# CC254x_Board1.net
KiCad netlist of a schematic drawn in Altium Designer
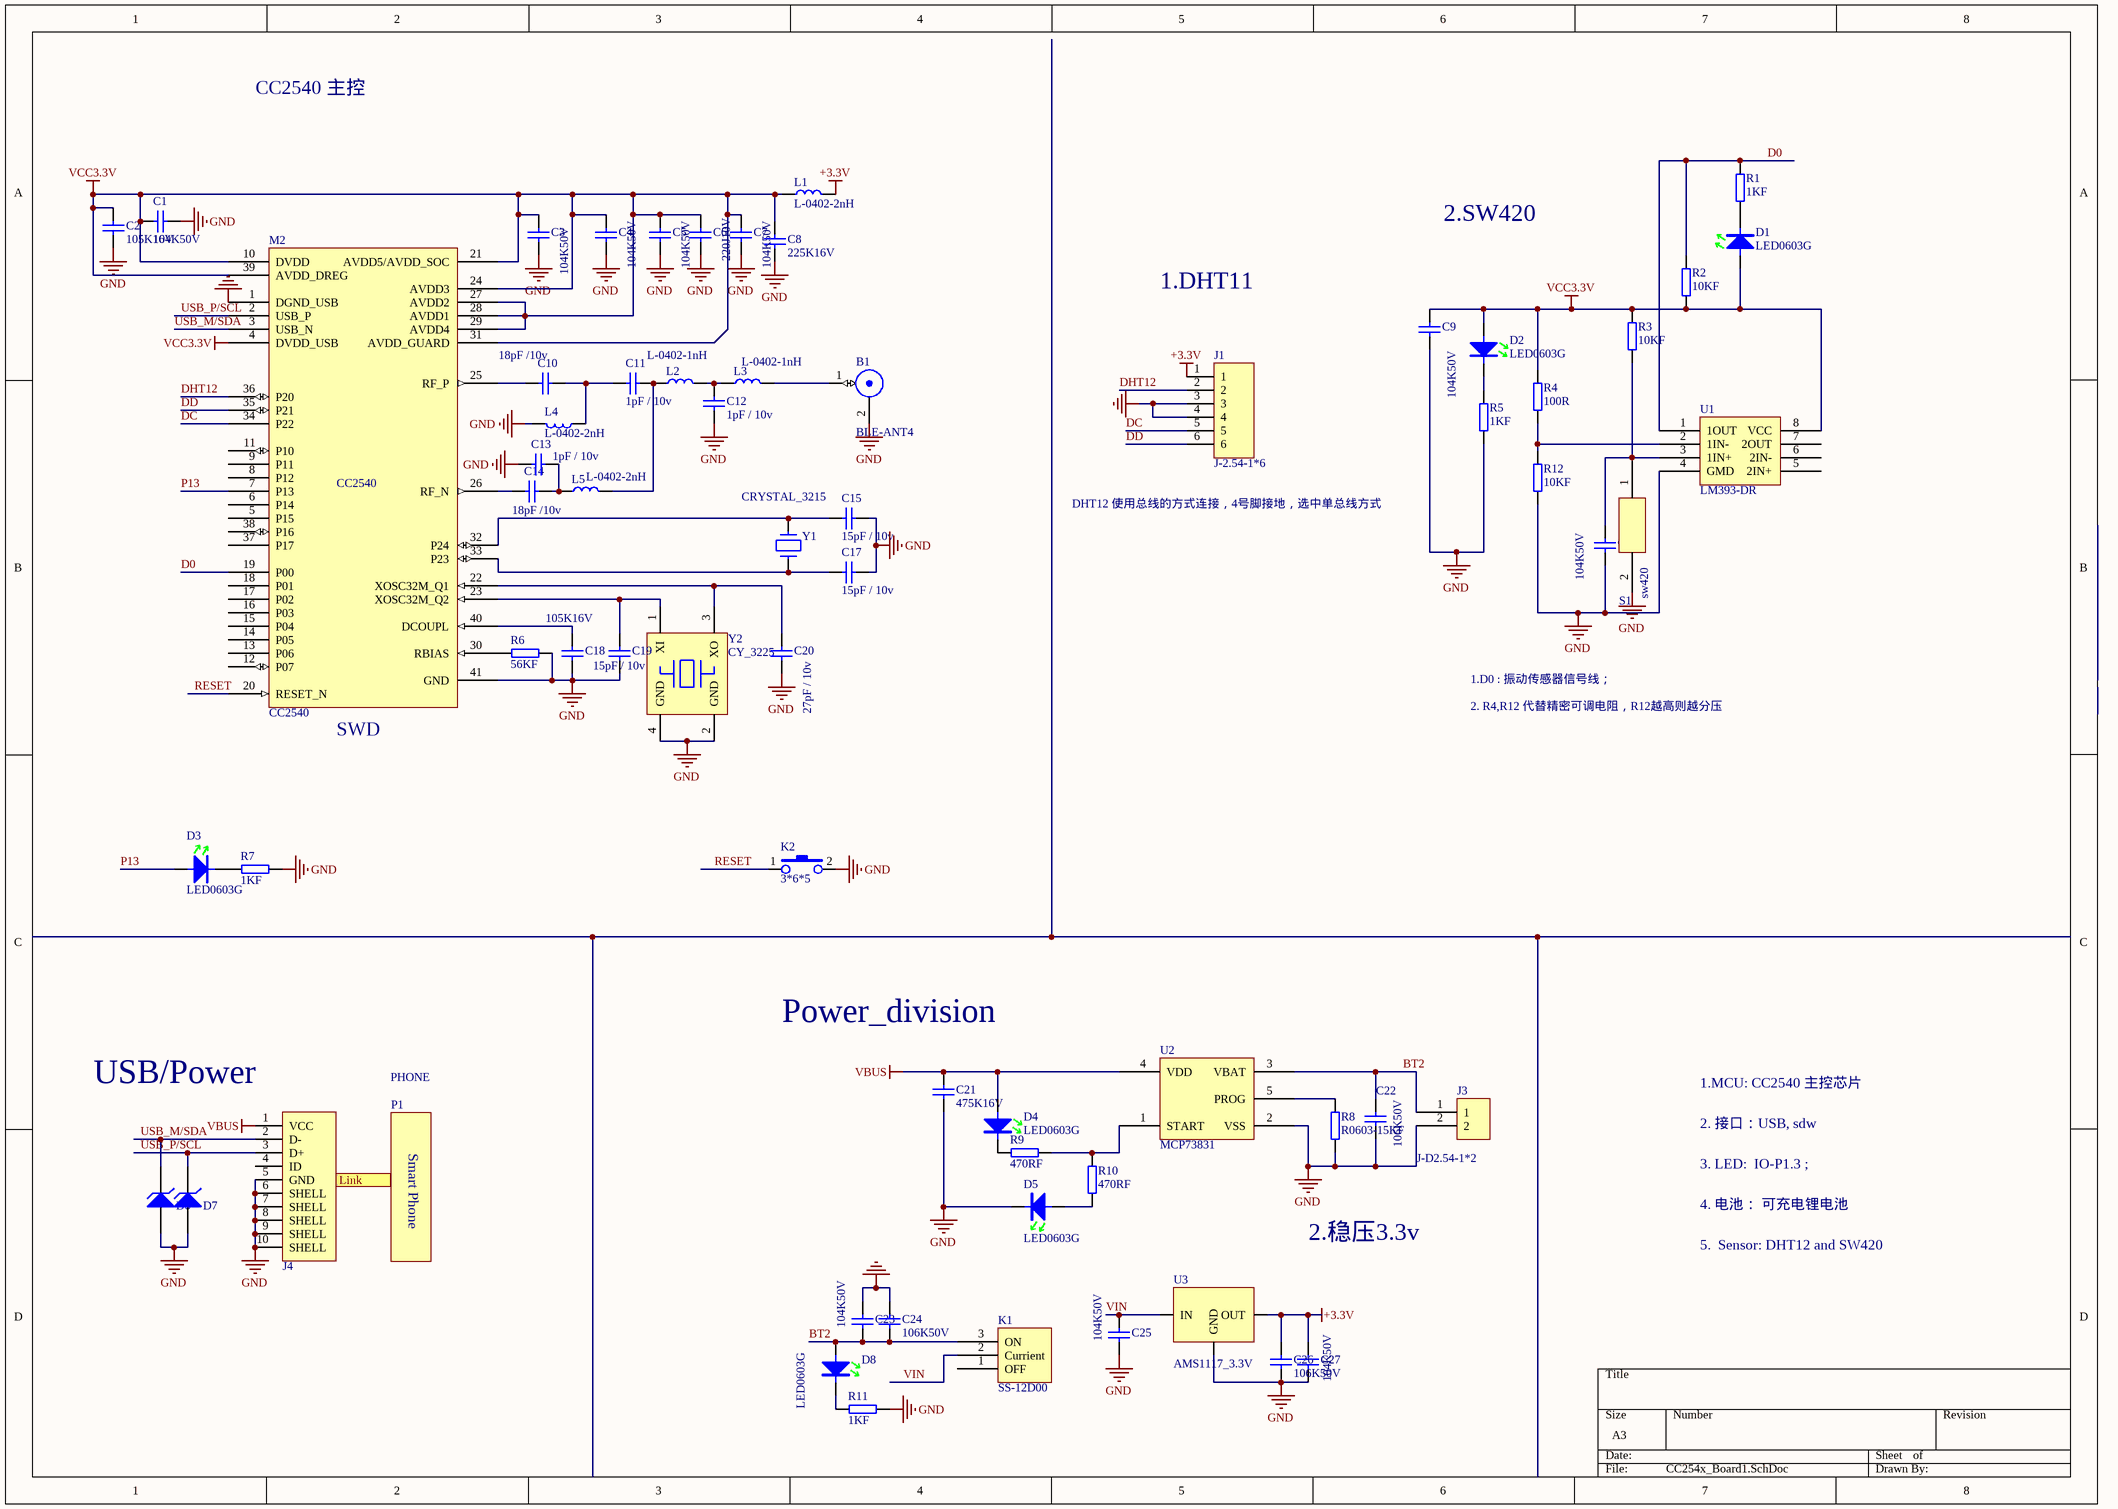
[diagram p0: CC254x_Board1.SchDoc]

(export (version "E")
  (design (tool "Eeschema 10.0.6"))
  (components
    (comp (ref "B1") (value "BLE-ANT4") (footprint "BLE-ANTS2") (libsource (lib "BleANT") (part "ANT")))
    (comp (ref "C1")
      (value "104K50V")
      (footprint "C0603")
      (description "贴片电容-陶瓷")
      (libsource (lib "Capacitor") (part "C0603X7R-104K50V"))
    )
    (comp (ref "C2")
      (value "105K16V")
      (footprint "C0603")
      (description "贴片电容-陶瓷")
      (libsource (lib "Capacitor") (part "C0603X7R-105K16V"))
    )
    (comp (ref "C3")
      (value "104K50V")
      (footprint "C0603")
      (description "贴片电容-陶瓷")
      (libsource (lib "Capacitor") (part "C0603X7R-104K50V"))
    )
    (comp (ref "C4")
      (value "104K50V")
      (footprint "C0603")
      (description "贴片电容-陶瓷")
      (libsource (lib "Capacitor") (part "C0603X7R-104K50V"))
    )
    (comp (ref "C5")
      (value "104K50V")
      (footprint "C0603")
      (description "贴片电容-陶瓷")
      (libsource (lib "Capacitor") (part "C0603X7R-104K50V"))
    )
    (comp (ref "C6")
      (value "220J10V")
      (footprint "C0402")
      (description "贴片电容-陶瓷")
      (libsource (lib "Capacitor") (part "C0402X7R-220J10V"))
    )
    (comp (ref "C7")
      (value "104K50V")
      (footprint "C0603")
      (description "贴片电容-陶瓷")
      (libsource (lib "Capacitor") (part "C0603X7R-104K50V"))
    )
    (comp (ref "C8")
      (value "225K16V")
      (footprint "C0603")
      (description "贴片电容-陶瓷")
      (libsource (lib "Capacitor") (part "C0603X7R-225K16V"))
    )
    (comp (ref "C9")
      (value "104K50V")
      (footprint "C0603")
      (description "贴片电容-陶瓷")
      (libsource (lib "Capacitor") (part "C0603X7R-104K50V"))
    )
    (comp (ref "C10")
      (value "18pF /10v")
      (footprint "C0402")
      (description "贴片电容-陶瓷")
      (libsource (lib "Capacitor") (part "C0402X7R-101J10V"))
    )
    (comp (ref "C11")
      (value "1pF / 10v")
      (footprint "C0402")
      (description "贴片电容-陶瓷")
      (libsource (lib "Capacitor") (part "C0402X7R-101J10V"))
    )
    (comp (ref "C12")
      (value "1pF / 10v")
      (footprint "C0402")
      (description "贴片电容-陶瓷")
      (libsource (lib "Capacitor") (part "C0402X7R-101J10V"))
    )
    (comp (ref "C13")
      (value "1pF / 10v")
      (footprint "C0402")
      (description "贴片电容-陶瓷")
      (libsource (lib "Capacitor") (part "C0402X7R-101J10V"))
    )
    (comp (ref "C14")
      (value "18pF /10v")
      (footprint "C0402")
      (description "贴片电容-陶瓷")
      (libsource (lib "Capacitor") (part "C0402X7R-101J10V"))
    )
    (comp (ref "C15")
      (value "15pF / 10v")
      (footprint "C0402")
      (description "贴片电容-陶瓷")
      (libsource (lib "Capacitor") (part "C0402X7R-101J10V"))
    )
    (comp (ref "C16")
      (value "104K50V")
      (footprint "C0603")
      (description "贴片电容-陶瓷")
      (libsource (lib "Capacitor") (part "C0603X7R-104K50V"))
    )
    (comp (ref "C17")
      (value "15pF / 10v")
      (footprint "C0402")
      (description "贴片电容-陶瓷")
      (libsource (lib "Capacitor") (part "C0402X7R-101J10V"))
    )
    (comp (ref "C18")
      (value "105K16V")
      (footprint "C0603")
      (description "贴片电容-陶瓷")
      (libsource (lib "Capacitor") (part "C0603X7R-105K16V"))
    )
    (comp (ref "C19")
      (value "15pF / 10v")
      (footprint "C0402")
      (description "贴片电容-陶瓷")
      (libsource (lib "Capacitor") (part "C0402X7R-101J10V"))
    )
    (comp (ref "C20")
      (value "27pF / 10v")
      (footprint "C0402")
      (description "贴片电容-陶瓷")
      (libsource (lib "Capacitor") (part "C0402X7R-101J10V"))
    )
    (comp (ref "C21")
      (value "475K16V")
      (footprint "C0603")
      (description "贴片电容-陶瓷")
      (libsource (lib "Capacitor") (part "C0603X7R-475K16V"))
    )
    (comp (ref "C22")
      (value "106K50V")
      (footprint "C0603")
      (description "贴片电容-陶瓷")
      (libsource (lib "Capacitor") (part "C0603X7R-106K50V"))
    )
    (comp (ref "C23")
      (value "104K50V")
      (footprint "C0603")
      (description "贴片电容-陶瓷")
      (libsource (lib "Capacitor") (part "C0603X7R-104K50V"))
    )
    (comp (ref "C24")
      (value "106K50V")
      (footprint "C0603")
      (description "贴片电容-陶瓷")
      (libsource (lib "Capacitor") (part "C0603X7R-106K50V"))
    )
    (comp (ref "C25")
      (value "104K50V")
      (footprint "C0603")
      (description "贴片电容-陶瓷")
      (libsource (lib "Capacitor") (part "C0603X7R-104K50V"))
    )
    (comp (ref "C26")
      (value "106K50V")
      (footprint "C0603")
      (description "贴片电容-陶瓷")
      (libsource (lib "Capacitor") (part "C0603X7R-106K50V"))
    )
    (comp (ref "C27")
      (value "104K50V")
      (footprint "C0603")
      (description "贴片电容-陶瓷")
      (libsource (lib "Capacitor") (part "C0603X7R-104K50V"))
    )
    (comp (ref "D1")
      (value "LED0603G")
      (footprint "D-LED0603G")
      (description "贴片二极管-LED")
      (libsource (lib "Diode") (part "DLED-0603-G"))
    )
    (comp (ref "D2")
      (value "LED0603G")
      (footprint "D-LED0603G")
      (description "贴片二极管-LED")
      (libsource (lib "Diode") (part "DLED-0603-G"))
    )
    (comp (ref "D3")
      (value "LED0603G")
      (footprint "D-LED0603G")
      (description "贴片二极管-LED")
      (libsource (lib "aiwacV2.0") (part "DLED-0603-G"))
    )
    (comp (ref "D4")
      (value "LED0603G")
      (footprint "D-LED0603G")
      (description "贴片二极管-LED")
      (libsource (lib "Diode") (part "DLED-0603-G"))
    )
    (comp (ref "D5")
      (value "LED0603G")
      (footprint "D-LED0603G")
      (description "贴片二极管-LED")
      (libsource (lib "Diode") (part "DLED-0603-G"))
    )
    (comp (ref "D6")
      (value "ESDA_TR1/0603")
      (footprint "HS_0603D")
      (description "Zener Diode")
      (fields (field (name "PUBLISHER") "*"))
      (libsource (lib "aiwacV2.0") (part "D Zener"))
    )
    (comp (ref "D7")
      (value "ESDA_TR1/0603")
      (footprint "HS_0603D")
      (description "Zener Diode")
      (fields (field (name "PUBLISHER") "*"))
      (libsource (lib "aiwacV2.0") (part "D Zener"))
    )
    (comp (ref "D8")
      (value "LED0603G")
      (footprint "D-LED0603G")
      (description "贴片二极管-LED")
      (libsource (lib "aiwacV2.0") (part "DLED-0603-G"))
    )
    (comp (ref "J1")
      (value "J-2.54-1*6")
      (footprint "D2.54-1*6")
      (description "单排")
      (libsource (lib "Connector") (part "J-2.54-6"))
    )
    (comp (ref "J3")
      (value "J-D2.54-1*2")
      (footprint "D2.54-1*2P")
      (libsource (lib "Connector") (part "J-D2.54-1*2单排"))
    )
    (comp (ref "J4")
      (value "USB-MINI-SOCKET")
      (footprint "MICRO-USB - 5.9")
      (description "USB-A卧式插座")
      (libsource (lib "epic2") (part "J-USB-MINI-SOCKET"))
    )
    (comp (ref "K1")
      (value "SS-12D00")
      (footprint "SS-12D00")
      (libsource (lib "Key") (part "SS-12D00(1P2T) 立式 柄高5MM"))
    )
    (comp (ref "K2")
      (value "3*6*5")
      (footprint "S-K3*6")
      (description "贴片-卧式轻触开关")
      (libsource (lib "Key") (part "3*6*5"))
    )
    (comp (ref "L1")
      (value "L-0402-2nH")
      (footprint "L0402")
      (description "贴片电感-层叠")
      (libsource (lib "magnetic") (part "L-0402-2nH"))
    )
    (comp (ref "L2")
      (value "L-0402-1nH")
      (footprint "L0402")
      (description "贴片电感-层叠")
      (libsource (lib "magnetic") (part "L-0402-2.2nH"))
    )
    (comp (ref "L3")
      (value "L-0402-1nH")
      (footprint "L0402")
      (description "贴片电感-层叠")
      (libsource (lib "magnetic") (part "L-0402-2.2nH"))
    )
    (comp (ref "L4")
      (value "L-0402-2nH")
      (footprint "L0402")
      (description "贴片电感-层叠")
      (libsource (lib "magnetic") (part "L-0402-2nH"))
    )
    (comp (ref "L5")
      (value "L-0402-2nH")
      (footprint "L0402")
      (description "贴片电感-层叠")
      (libsource (lib "magnetic") (part "L-0402-2nH"))
    )
    (comp (ref "M2")
      (value "CC2540")
      (footprint "CC254X_QFN")
      (libsource (lib "CC254xEM-sch") (part "CC2540"))
    )
    (comp (ref "P1") (value "PHONE") (libsource (lib "epic") (part "PHONE")))
    (comp (ref "R1")
      (value "1KF")
      (footprint "R0603")
      (description "贴片电阻-通用")
      (libsource (lib "Resistor") (part "R0603-1KF"))
    )
    (comp (ref "R2")
      (value "10KF")
      (footprint "R0603")
      (description "贴片电阻-通用")
      (libsource (lib "Resistor") (part "R0603-10KF"))
    )
    (comp (ref "R3")
      (value "10KF")
      (footprint "R0603")
      (description "贴片电阻-通用")
      (libsource (lib "Resistor") (part "R0603-10KF"))
    )
    (comp (ref "R4")
      (value "100R")
      (footprint "R0603")
      (description "贴片电阻-通用")
      (libsource (lib "Resistor") (part "R0603-10KF"))
    )
    (comp (ref "R5")
      (value "1KF")
      (footprint "R0603")
      (description "贴片电阻-通用")
      (libsource (lib "Resistor") (part "R0603-1KF"))
    )
    (comp (ref "R6")
      (value "56KF")
      (footprint "R0603")
      (description "贴片电阻-通用")
      (libsource (lib "Resistor") (part "R0603-47KF"))
    )
    (comp (ref "R7")
      (value "1KF")
      (footprint "R0603")
      (description "贴片电阻-通用")
      (libsource (lib "Resistor") (part "R0603-1KF"))
    )
    (comp (ref "R8")
      (value "R0603-15KF")
      (footprint "R0603")
      (description "贴片电容-通用")
      (libsource (lib "Resistor") (part "R0603-15KF"))
    )
    (comp (ref "R9")
      (value "470RF")
      (footprint "R0603")
      (description "贴片电阻-通用")
      (libsource (lib "Resistor") (part "R0603-470RF"))
    )
    (comp (ref "R10")
      (value "470RF")
      (footprint "R0603")
      (description "贴片电阻-通用")
      (libsource (lib "Resistor") (part "R0603-470RF"))
    )
    (comp (ref "R11")
      (value "1KF")
      (footprint "R0603")
      (description "贴片电阻-通用")
      (libsource (lib "Resistor") (part "R0603-1KF"))
    )
    (comp (ref "R12")
      (value "10KF")
      (footprint "R0603")
      (description "贴片电阻-通用")
      (libsource (lib "Resistor") (part "R0603-10KF"))
    )
    (comp (ref "S1")
      (value "sw420")
      (footprint "sw420")
      (description "常闭振动传感器")
      (libsource (lib "sensor") (part "sw420"))
    )
    (comp (ref "U1")
      (value "LM393-DR")
      (footprint "LM393")
      (description "双路比较器")
      (libsource (lib "IC") (part "LM393-DR"))
    )
    (comp (ref "U2")
      (value "MCP73831")
      (footprint "SOT23-5N")
      (description "charge IC")
      (libsource (lib "IC") (part "MCP73831"))
    )
    (comp (ref "U3")
      (value "AMS1117_3.3V")
      (footprint "SOT-223")
      (libsource (lib "IC") (part "AMS1117-3.3V"))
    )
    (comp (ref "Y1")
      (value "CRYSTAL_3215")
      (footprint "CRYSTAL_3215")
      (description "CRYSTAL_3215，两脚")
      (libsource (lib "oscillator") (part "CRYSTAL_3215"))
    )
    (comp (ref "Y2") (value "CY_3225") (footprint "CY_3225") (libsource (lib "oscillator") (part "CY_3225")))
  )
  (nets
    (net (code "1") (name "+3.3V") (class "Default")
      (node (ref "C26") (pin "2") (pinfunction "2_2") (pintype "passive"))
      (node (ref "C27") (pin "1") (pinfunction "1_1") (pintype "passive"))
      (node (ref "J1") (pin "1") (pinfunction "1_1") (pintype "passive"))
      (node (ref "L1") (pin "2") (pinfunction "2_2") (pintype "passive"))
      (node (ref "U3") (pin "2") (pinfunction "OUT_2") (pintype "passive"))
    )
    (net (code "2") (name "/BT2") (class "Default")
      (node (ref "C22") (pin "1") (pinfunction "1_1") (pintype "passive"))
      (node (ref "C23") (pin "2") (pinfunction "2_2") (pintype "passive"))
      (node (ref "C24") (pin "1") (pinfunction "1_1") (pintype "passive"))
      (node (ref "D8") (pin "1") (pinfunction "1_1") (pintype "passive"))
      (node (ref "J3") (pin "1") (pinfunction "1_1") (pintype "passive"))
      (node (ref "K1") (pin "3") (pinfunction "ON_3") (pintype "passive"))
      (node (ref "U2") (pin "3") (pinfunction "VBAT_3") (pintype "passive"))
    )
    (net (code "3") (name "/D0") (class "Default")
      (node (ref "M2") (pin "19") (pinfunction "P00_19") (pintype "passive"))
      (node (ref "R1") (pin "1") (pinfunction "1_1") (pintype "passive"))
      (node (ref "R2") (pin "2") (pinfunction "2_2") (pintype "passive"))
      (node (ref "U1") (pin "1") (pinfunction "1OUT_1") (pintype "passive"))
    )
    (net (code "4") (name "/DC") (class "Default")
      (node (ref "J1") (pin "5") (pinfunction "5_5") (pintype "passive"))
      (node (ref "M2") (pin "34") (pinfunction "P22_34") (pintype "passive"))
    )
    (net (code "5") (name "/DD") (class "Default")
      (node (ref "J1") (pin "6") (pinfunction "6_6") (pintype "passive"))
      (node (ref "M2") (pin "35") (pinfunction "P21_35") (pintype "bidirectional"))
    )
    (net (code "6") (name "/DHT12") (class "Default")
      (node (ref "J1") (pin "2") (pinfunction "2_2") (pintype "passive"))
      (node (ref "M2") (pin "36") (pinfunction "P20_36") (pintype "bidirectional"))
    )
    (net (code "8") (name "/P13") (class "Default")
      (node (ref "D3") (pin "1") (pinfunction "1_1") (pintype "passive"))
      (node (ref "M2") (pin "7") (pinfunction "P13_7") (pintype "passive"))
    )
    (net (code "9") (name "/RESET") (class "Default")
      (node (ref "K2") (pin "1") (pinfunction "1_1") (pintype "passive"))
      (node (ref "M2") (pin "20") (pinfunction "RESET_N_20") (pintype "input"))
    )
    (net (code "10") (name "/USB_M{slash}SDA") (class "Default")
      (node (ref "D6") (pin "2") (pinfunction "K_2") (pintype "passive"))
      (node (ref "J4") (pin "2") (pinfunction "D-_2") (pintype "passive"))
      (node (ref "M2") (pin "3") (pinfunction "USB_N_3") (pintype "power_in"))
    )
    (net (code "11") (name "/USB_P{slash}SCL") (class "Default")
      (node (ref "D7") (pin "2") (pinfunction "K_2") (pintype "passive"))
      (node (ref "J4") (pin "3") (pinfunction "D+_3") (pintype "passive"))
      (node (ref "M2") (pin "2") (pinfunction "USB_P_2") (pintype "power_in"))
    )
    (net (code "12") (name "/VIN") (class "Default")
      (node (ref "C25") (pin "1") (pinfunction "1_1") (pintype "passive"))
      (node (ref "K1") (pin "2") (pinfunction "Currient_2") (pintype "passive"))
      (node (ref "U3") (pin "3") (pinfunction "IN_3") (pintype "passive"))
    )
    (net (code "13") (name "GND") (class "Default")
      (node (ref "B1") (pin "2") (pinfunction "2_2") (pintype "power_in"))
      (node (ref "C1") (pin "2") (pinfunction "2_2") (pintype "passive"))
      (node (ref "C12") (pin "2") (pinfunction "2_2") (pintype "passive"))
      (node (ref "C13") (pin "2") (pinfunction "2_2") (pintype "passive"))
      (node (ref "C15") (pin "2") (pinfunction "2_2") (pintype "passive"))
      (node (ref "C16") (pin "2") (pinfunction "2_2") (pintype "passive"))
      (node (ref "C17") (pin "2") (pinfunction "2_2") (pintype "passive"))
      (node (ref "C18") (pin "1") (pinfunction "1_1") (pintype "passive"))
      (node (ref "C19") (pin "2") (pinfunction "2_2") (pintype "passive"))
      (node (ref "C2") (pin "1") (pinfunction "1_1") (pintype "passive"))
      (node (ref "C20") (pin "2") (pinfunction "2_2") (pintype "passive"))
      (node (ref "C21") (pin "2") (pinfunction "2_2") (pintype "passive"))
      (node (ref "C22") (pin "2") (pinfunction "2_2") (pintype "passive"))
      (node (ref "C23") (pin "1") (pinfunction "1_1") (pintype "passive"))
      (node (ref "C24") (pin "2") (pinfunction "2_2") (pintype "passive"))
      (node (ref "C25") (pin "2") (pinfunction "2_2") (pintype "passive"))
      (node (ref "C26") (pin "1") (pinfunction "1_1") (pintype "passive"))
      (node (ref "C27") (pin "2") (pinfunction "2_2") (pintype "passive"))
      (node (ref "C3") (pin "1") (pinfunction "1_1") (pintype "passive"))
      (node (ref "C4") (pin "1") (pinfunction "1_1") (pintype "passive"))
      (node (ref "C5") (pin "1") (pinfunction "1_1") (pintype "passive"))
      (node (ref "C6") (pin "2") (pinfunction "2_2") (pintype "passive"))
      (node (ref "C7") (pin "1") (pinfunction "1_1") (pintype "passive"))
      (node (ref "C8") (pin "2") (pinfunction "2_2") (pintype "passive"))
      (node (ref "C9") (pin "2") (pinfunction "2_2") (pintype "passive"))
      (node (ref "D5") (pin "2") (pinfunction "2_2") (pintype "passive"))
      (node (ref "D6") (pin "1") (pinfunction "A_1") (pintype "passive"))
      (node (ref "D7") (pin "1") (pinfunction "A_1") (pintype "passive"))
      (node (ref "J1") (pin "3") (pinfunction "3_3") (pintype "passive"))
      (node (ref "J1") (pin "4") (pinfunction "4_4") (pintype "passive"))
      (node (ref "J3") (pin "2") (pinfunction "2_2") (pintype "passive"))
      (node (ref "J4") (pin "10") (pinfunction "SHELL_10") (pintype "passive"))
      (node (ref "J4") (pin "5") (pinfunction "GND_5") (pintype "passive"))
      (node (ref "J4") (pin "6") (pinfunction "SHELL_6") (pintype "passive"))
      (node (ref "J4") (pin "7") (pinfunction "SHELL_7") (pintype "passive"))
      (node (ref "J4") (pin "8") (pinfunction "SHELL_8") (pintype "passive"))
      (node (ref "J4") (pin "9") (pinfunction "SHELL_9") (pintype "passive"))
      (node (ref "K2") (pin "2") (pinfunction "2_2") (pintype "passive"))
      (node (ref "L4") (pin "2") (pinfunction "2_2") (pintype "passive"))
      (node (ref "M2") (pin "1") (pinfunction "DGND_USB_1") (pintype "power_in"))
      (node (ref "M2") (pin "41") (pinfunction "GND_41") (pintype "power_in"))
      (node (ref "R11") (pin "2") (pinfunction "2_2") (pintype "passive"))
      (node (ref "R12") (pin "1") (pinfunction "1_1") (pintype "passive"))
      (node (ref "R5") (pin "1") (pinfunction "1_1") (pintype "passive"))
      (node (ref "R6") (pin "2") (pinfunction "2_2") (pintype "passive"))
      (node (ref "R7") (pin "2") (pinfunction "2_2") (pintype "passive"))
      (node (ref "R8") (pin "1") (pinfunction "1_1") (pintype "passive"))
      (node (ref "U1") (pin "4") (pinfunction "GMD_4") (pintype "passive"))
      (node (ref "U2") (pin "2") (pinfunction "VSS_2") (pintype "passive"))
      (node (ref "U3") (pin "1") (pinfunction "GND_1") (pintype "passive"))
      (node (ref "Y2") (pin "2") (pinfunction "GND_2") (pintype "passive"))
      (node (ref "Y2") (pin "4") (pinfunction "GND_4") (pintype "passive"))
    )
    (net (code "14") (name "Net-(B1-Pad1)") (class "Default")
      (node (ref "B1") (pin "1") (pinfunction "1_1") (pintype "bidirectional"))
      (node (ref "L3") (pin "2") (pinfunction "2_2") (pintype "passive"))
    )
    (net (code "15") (name "Net-(C10-Pad1)") (class "Default")
      (node (ref "C10") (pin "1") (pinfunction "1_1") (pintype "passive"))
      (node (ref "C11") (pin "2") (pinfunction "2_2") (pintype "passive"))
      (node (ref "L4") (pin "1") (pinfunction "1_1") (pintype "passive"))
    )
    (net (code "16") (name "Net-(C11-Pad1)") (class "Default")
      (node (ref "C11") (pin "1") (pinfunction "1_1") (pintype "passive"))
      (node (ref "L2") (pin "1") (pinfunction "1_1") (pintype "passive"))
      (node (ref "L5") (pin "2") (pinfunction "2_2") (pintype "passive"))
    )
    (net (code "17") (name "Net-(C12-Pad1)") (class "Default")
      (node (ref "C12") (pin "1") (pinfunction "1_1") (pintype "passive"))
      (node (ref "L2") (pin "2") (pinfunction "2_2") (pintype "passive"))
      (node (ref "L3") (pin "1") (pinfunction "1_1") (pintype "passive"))
    )
    (net (code "18") (name "Net-(C13-Pad1)") (class "Default")
      (node (ref "C13") (pin "1") (pinfunction "1_1") (pintype "passive"))
      (node (ref "C14") (pin "1") (pinfunction "1_1") (pintype "passive"))
      (node (ref "L5") (pin "1") (pinfunction "1_1") (pintype "passive"))
    )
    (net (code "19") (name "Net-(D1-Pad2)") (class "Default")
      (node (ref "D1") (pin "2") (pinfunction "2_2") (pintype "passive"))
      (node (ref "R1") (pin "2") (pinfunction "2_2") (pintype "passive"))
    )
    (net (code "20") (name "Net-(D2-Pad2)") (class "Default")
      (node (ref "D2") (pin "2") (pinfunction "2_2") (pintype "passive"))
      (node (ref "R5") (pin "2") (pinfunction "2_2") (pintype "passive"))
    )
    (net (code "21") (name "Net-(D3-Pad2)") (class "Default")
      (node (ref "D3") (pin "2") (pinfunction "2_2") (pintype "passive"))
      (node (ref "R7") (pin "1") (pinfunction "1_1") (pintype "passive"))
    )
    (net (code "22") (name "Net-(D4-Pad2)") (class "Default")
      (node (ref "D4") (pin "2") (pinfunction "2_2") (pintype "passive"))
      (node (ref "R9") (pin "1") (pinfunction "1_1") (pintype "passive"))
    )
    (net (code "23") (name "Net-(D5-Pad1)") (class "Default")
      (node (ref "D5") (pin "1") (pinfunction "1_1") (pintype "passive"))
      (node (ref "R10") (pin "1") (pinfunction "1_1") (pintype "passive"))
    )
    (net (code "24") (name "Net-(D8-Pad2)") (class "Default")
      (node (ref "D8") (pin "2") (pinfunction "2_2") (pintype "passive"))
      (node (ref "R11") (pin "1") (pinfunction "1_1") (pintype "passive"))
    )
    (net (code "25") (name "Net-(M2-DCOUPL)") (class "Default")
      (node (ref "C18") (pin "2") (pinfunction "2_2") (pintype "passive"))
      (node (ref "M2") (pin "40") (pinfunction "DCOUPL_40") (pintype "input"))
    )
    (net (code "26") (name "Net-(M2-P23)") (class "Default")
      (node (ref "C17") (pin "1") (pinfunction "1_1") (pintype "passive"))
      (node (ref "M2") (pin "33") (pinfunction "P23_33") (pintype "bidirectional"))
      (node (ref "Y1") (pin "1") (pinfunction "1_1") (pintype "passive"))
    )
    (net (code "27") (name "Net-(M2-P24)") (class "Default")
      (node (ref "C15") (pin "1") (pinfunction "1_1") (pintype "passive"))
      (node (ref "M2") (pin "32") (pinfunction "P24_32") (pintype "bidirectional"))
      (node (ref "Y1") (pin "2") (pinfunction "2_2") (pintype "passive"))
    )
    (net (code "28") (name "Net-(M2-RBIAS)") (class "Default")
      (node (ref "M2") (pin "30") (pinfunction "RBIAS_30") (pintype "input"))
      (node (ref "R6") (pin "1") (pinfunction "1_1") (pintype "passive"))
    )
    (net (code "29") (name "Net-(M2-RF_N)") (class "Default")
      (node (ref "C14") (pin "2") (pinfunction "2_2") (pintype "passive"))
      (node (ref "M2") (pin "26") (pinfunction "RF_N_26") (pintype "output"))
    )
    (net (code "30") (name "Net-(M2-RF_P)") (class "Default")
      (node (ref "C10") (pin "2") (pinfunction "2_2") (pintype "passive"))
      (node (ref "M2") (pin "25") (pinfunction "RF_P_25") (pintype "output"))
    )
    (net (code "31") (name "Net-(M2-XOSC32M_Q1)") (class "Default")
      (node (ref "C20") (pin "1") (pinfunction "1_1") (pintype "passive"))
      (node (ref "M2") (pin "22") (pinfunction "XOSC32M_Q1_22") (pintype "input"))
      (node (ref "Y2") (pin "3") (pinfunction "XO_3") (pintype "passive"))
    )
    (net (code "32") (name "Net-(M2-XOSC32M_Q2)") (class "Default")
      (node (ref "C19") (pin "1") (pinfunction "1_1") (pintype "passive"))
      (node (ref "M2") (pin "23") (pinfunction "XOSC32M_Q2_23") (pintype "input"))
      (node (ref "Y2") (pin "1") (pinfunction "XI_1") (pintype "passive"))
    )
    (net (code "33") (name "Net-(U1-1IN+)") (class "Default")
      (node (ref "C16") (pin "1") (pinfunction "1_1") (pintype "passive"))
      (node (ref "R3") (pin "1") (pinfunction "1_1") (pintype "passive"))
      (node (ref "S1") (pin "1") (pinfunction "1_1") (pintype "passive"))
      (node (ref "U1") (pin "3") (pinfunction "1IN+_3") (pintype "passive"))
    )
    (net (code "34") (name "Net-(U1-1IN-)") (class "Default")
      (node (ref "R12") (pin "2") (pinfunction "2_2") (pintype "passive"))
      (node (ref "R4") (pin "1") (pinfunction "1_1") (pintype "passive"))
      (node (ref "U1") (pin "2") (pinfunction "1IN-_2") (pintype "passive"))
    )
    (net (code "35") (name "Net-(U2-PROG)") (class "Default")
      (node (ref "R8") (pin "2") (pinfunction "2_2") (pintype "passive"))
      (node (ref "U2") (pin "5") (pinfunction "PROG_5") (pintype "passive"))
    )
    (net (code "36") (name "Net-(U2-START)") (class "Default")
      (node (ref "R10") (pin "2") (pinfunction "2_2") (pintype "passive"))
      (node (ref "R9") (pin "2") (pinfunction "2_2") (pintype "passive"))
      (node (ref "U2") (pin "1") (pinfunction "START_1") (pintype "passive"))
    )
    (net (code "37") (name "VBUS") (class "Default")
      (node (ref "C21") (pin "1") (pinfunction "1_1") (pintype "passive"))
      (node (ref "D4") (pin "1") (pinfunction "1_1") (pintype "passive"))
      (node (ref "J4") (pin "1") (pinfunction "VCC_1") (pintype "passive"))
      (node (ref "U2") (pin "4") (pinfunction "VDD_4") (pintype "passive"))
    )
    (net (code "38") (name "VCC3.3V") (class "Default")
      (node (ref "C1") (pin "1") (pinfunction "1_1") (pintype "passive"))
      (node (ref "C2") (pin "2") (pinfunction "2_2") (pintype "passive"))
      (node (ref "C3") (pin "2") (pinfunction "2_2") (pintype "passive"))
      (node (ref "C4") (pin "2") (pinfunction "2_2") (pintype "passive"))
      (node (ref "C5") (pin "2") (pinfunction "2_2") (pintype "passive"))
      (node (ref "C6") (pin "1") (pinfunction "1_1") (pintype "passive"))
      (node (ref "C7") (pin "2") (pinfunction "2_2") (pintype "passive"))
      (node (ref "C8") (pin "1") (pinfunction "1_1") (pintype "passive"))
      (node (ref "C9") (pin "1") (pinfunction "1_1") (pintype "passive"))
      (node (ref "D1") (pin "1") (pinfunction "1_1") (pintype "passive"))
      (node (ref "D2") (pin "1") (pinfunction "1_1") (pintype "passive"))
      (node (ref "L1") (pin "1") (pinfunction "1_1") (pintype "passive"))
      (node (ref "M2") (pin "10") (pinfunction "DVDD_10") (pintype "power_in"))
      (node (ref "M2") (pin "21") (pinfunction "AVDD5/AVDD_SOC_21") (pintype "power_in"))
      (node (ref "M2") (pin "24") (pinfunction "AVDD3_24") (pintype "power_in"))
      (node (ref "M2") (pin "27") (pinfunction "AVDD2_27") (pintype "power_in"))
      (node (ref "M2") (pin "28") (pinfunction "AVDD1_28") (pintype "power_in"))
      (node (ref "M2") (pin "29") (pinfunction "AVDD4_29") (pintype "power_in"))
      (node (ref "M2") (pin "31") (pinfunction "AVDD_GUARD_31") (pintype "power_in"))
      (node (ref "M2") (pin "39") (pinfunction "AVDD_DREG_39") (pintype "power_in"))
      (node (ref "M2") (pin "4") (pinfunction "DVDD_USB_4") (pintype "power_in"))
      (node (ref "R2") (pin "1") (pinfunction "1_1") (pintype "passive"))
      (node (ref "R3") (pin "2") (pinfunction "2_2") (pintype "passive"))
      (node (ref "R4") (pin "2") (pinfunction "2_2") (pintype "passive"))
      (node (ref "U1") (pin "8") (pinfunction "VCC_8") (pintype "passive"))
    )
    (net (code "39") (name "unconnected-(J4-ID-Pad4)") (class "Default")
      (node (ref "J4") (pin "4") (pinfunction "ID_4") (pintype "passive"))
    )
    (net (code "40") (name "unconnected-(K1-OFF-Pad1)") (class "Default")
      (node (ref "K1") (pin "1") (pinfunction "OFF_1") (pintype "passive"))
    )
    (net (code "41") (name "unconnected-(M2-P01-Pad18)") (class "Default")
      (node (ref "M2") (pin "18") (pinfunction "P01_18") (pintype "passive"))
    )
    (net (code "42") (name "unconnected-(M2-P02-Pad17)") (class "Default")
      (node (ref "M2") (pin "17") (pinfunction "P02_17") (pintype "passive"))
    )
    (net (code "43") (name "unconnected-(M2-P03-Pad16)") (class "Default")
      (node (ref "M2") (pin "16") (pinfunction "P03_16") (pintype "passive"))
    )
    (net (code "44") (name "unconnected-(M2-P04-Pad15)") (class "Default")
      (node (ref "M2") (pin "15") (pinfunction "P04_15") (pintype "passive"))
    )
    (net (code "45") (name "unconnected-(M2-P05-Pad14)") (class "Default")
      (node (ref "M2") (pin "14") (pinfunction "P05_14") (pintype "passive"))
    )
    (net (code "46") (name "unconnected-(M2-P06-Pad13)") (class "Default")
      (node (ref "M2") (pin "13") (pinfunction "P06_13") (pintype "passive"))
    )
    (net (code "47") (name "unconnected-(M2-P07-Pad12)") (class "Default")
      (node (ref "M2") (pin "12") (pinfunction "P07_12") (pintype "bidirectional"))
    )
    (net (code "48") (name "unconnected-(M2-P10-Pad11)") (class "Default")
      (node (ref "M2") (pin "11") (pinfunction "P10_11") (pintype "bidirectional"))
    )
    (net (code "49") (name "unconnected-(M2-P11-Pad9)") (class "Default")
      (node (ref "M2") (pin "9") (pinfunction "P11_9") (pintype "passive"))
    )
    (net (code "50") (name "unconnected-(M2-P12-Pad8)") (class "Default")
      (node (ref "M2") (pin "8") (pinfunction "P12_8") (pintype "passive"))
    )
    (net (code "51") (name "unconnected-(M2-P14-Pad6)") (class "Default")
      (node (ref "M2") (pin "6") (pinfunction "P14_6") (pintype "passive"))
    )
    (net (code "52") (name "unconnected-(M2-P15-Pad5)") (class "Default")
      (node (ref "M2") (pin "5") (pinfunction "P15_5") (pintype "passive"))
    )
    (net (code "53") (name "unconnected-(M2-P16-Pad38)") (class "Default")
      (node (ref "M2") (pin "38") (pinfunction "P16_38") (pintype "bidirectional"))
    )
    (net (code "54") (name "unconnected-(M2-P17-Pad37)") (class "Default")
      (node (ref "M2") (pin "37") (pinfunction "P17_37") (pintype "passive"))
    )
    (net (code "55") (name "unconnected-(S1-Pad2)") (class "Default")
      (node (ref "S1") (pin "2") (pinfunction "2_2") (pintype "passive"))
    )
    (net (code "56") (name "unconnected-(U1-2IN+-Pad5)") (class "Default")
      (node (ref "U1") (pin "5") (pinfunction "2IN+_5") (pintype "passive"))
    )
    (net (code "57") (name "unconnected-(U1-2IN--Pad6)") (class "Default")
      (node (ref "U1") (pin "6") (pinfunction "2IN-_6") (pintype "passive"))
    )
    (net (code "58") (name "unconnected-(U1-2OUT-Pad7)") (class "Default")
      (node (ref "U1") (pin "7") (pinfunction "2OUT_7") (pintype "passive"))
    )
  )
)
